# ESP32-S3_Amplifier_and_IMU.net
KiCad netlist of a schematic drawn in Altium Designer
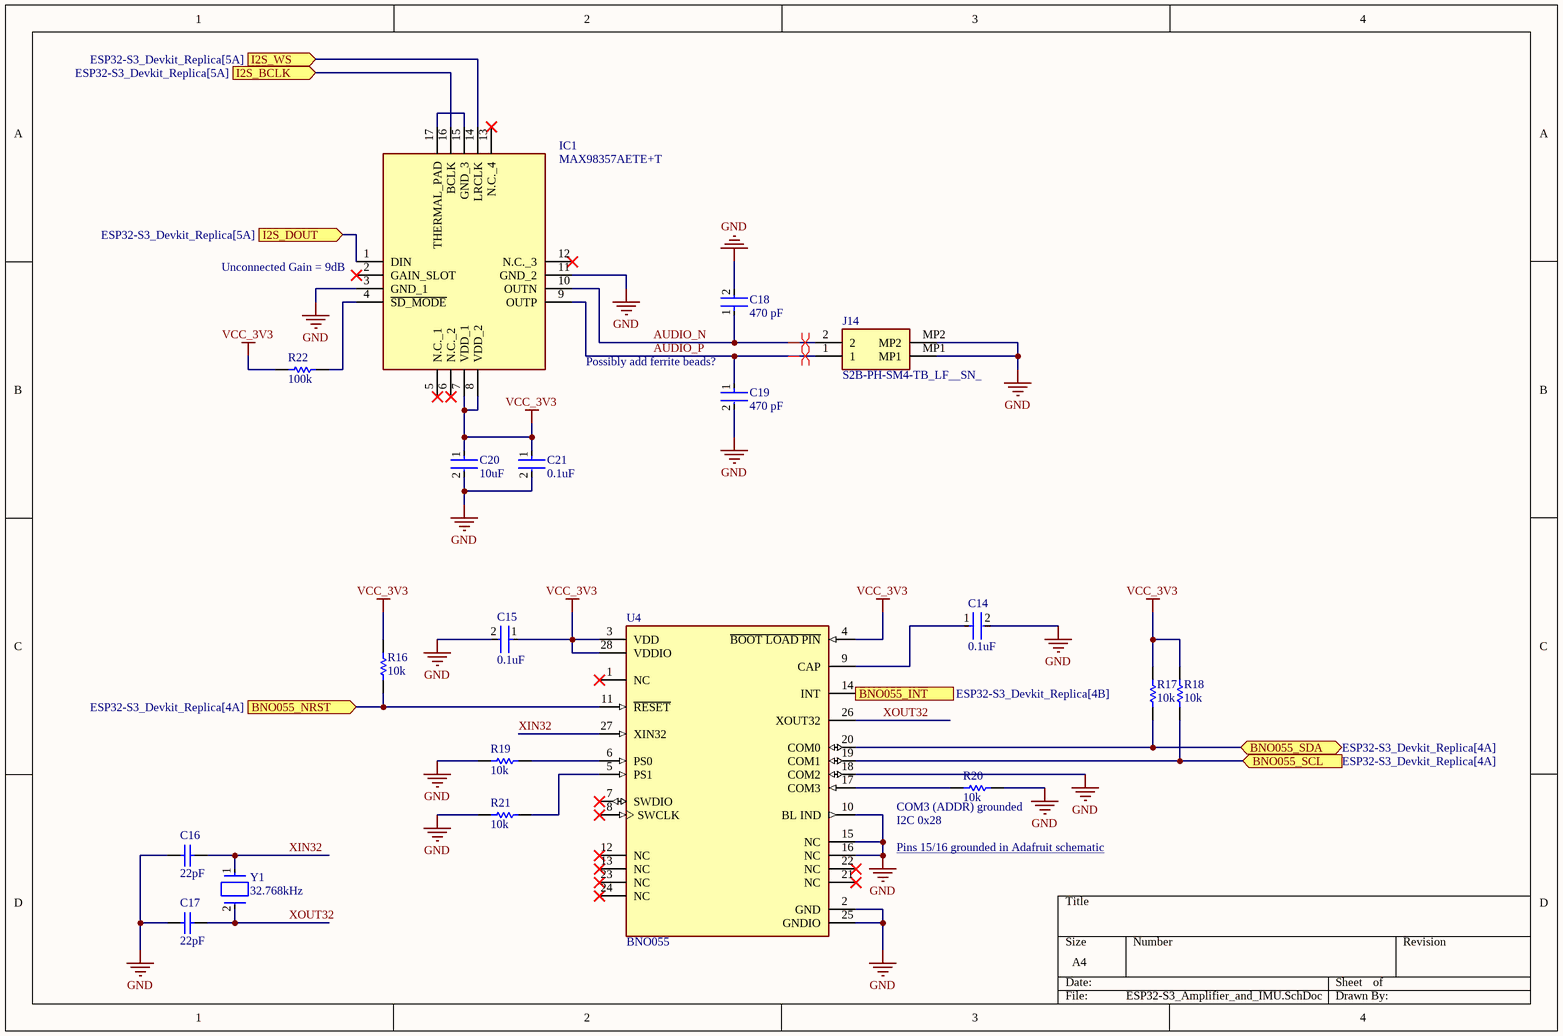
[diagram p0: ESP32-S3_Amplifier_and_IMU.SchDoc]

(export (version "E")
  (design (tool "Eeschema 10.0.6"))
  (components
    (comp (ref "C14")
      (value "C1005X7R1H104K050BB")
      (footprint "FP-C1005-050-0_05-IPC_C")
      (description "Multilayer Ceramic Capacitors 100nF ±10% 50V X7R SMD 0402")
      (fields
        (field (name "VOLTAGE") "50V")
        (field (name "CAPACITANCE") "0.1uF")
        (field (name "TOLERANCE") "10%")
      )
      (libsource (lib "Altium Content Vault") (part "b4654b650e69147ec39a6b967a45e02"))
    )
    (comp (ref "C15")
      (value "C1005X7R1H104K050BB")
      (footprint "FP-C1005-050-0_05-IPC_C")
      (description "Multilayer Ceramic Capacitors 100nF ±10% 50V X7R SMD 0402")
      (fields
        (field (name "VOLTAGE") "50V")
        (field (name "CAPACITANCE") "0.1uF")
        (field (name "TOLERANCE") "10%")
      )
      (libsource (lib "Altium Content Vault") (part "b4654b650e69147ec39a6b967a45e02"))
    )
    (comp (ref "C16")
      (value "CC0402JRNPO9BN220")
      (footprint "CAPC1005X55X25ML05T05")
      (description "Chip Capacitor, 22 pF, +/- 5%, 50 V, -55 to 125 degC, 0402 (1005 Metric), RoHS, Tape and Reel")
      (fields
        (field (name "CAPACITANCE") "22pF")
        (field (name "MANUFACTURER") "Yageo")
        (field (name "TOLERANCE") "5%")
      )
      (libsource (lib "Altium Content Vault") (part "CAP-NP-2"))
    )
    (comp (ref "C17")
      (value "CC0402JRNPO9BN220")
      (footprint "CAPC1005X55X25ML05T05")
      (description "Chip Capacitor, 22 pF, +/- 5%, 50 V, -55 to 125 degC, 0402 (1005 Metric), RoHS, Tape and Reel")
      (fields
        (field (name "CAPACITANCE") "22pF")
        (field (name "MANUFACTURER") "Yageo")
        (field (name "TOLERANCE") "5%")
      )
      (libsource (lib "Altium Content Vault") (part "CAP-NP-2"))
    )
    (comp (ref "C18")
      (value "C0402C471J5GACAUTO")
      (footprint "FP-C0402-BB-MFG")
      (description "CAP CER 470PF 50V C0G/NP0 0402")
      (fields
        (field (name "CAPACITANCE") "470 pF")
        (field (name "TOLERANCE") "0.05")
        (field (name "OCTOPART") "https://octopart.com/c0402c471j5gacauto-kemet-34993933")
      )
      (libsource (lib "Altium Content Vault") (part "b4654b650e69147ec39a6b967a45e02"))
    )
    (comp (ref "C19")
      (value "C0402C471J5GACAUTO")
      (footprint "FP-C0402-BB-MFG")
      (description "CAP CER 470PF 50V C0G/NP0 0402")
      (fields
        (field (name "CAPACITANCE") "470 pF")
        (field (name "TOLERANCE") "0.05")
        (field (name "OCTOPART") "https://octopart.com/c0402c471j5gacauto-kemet-34993933")
      )
      (libsource (lib "Altium Content Vault") (part "b4654b650e69147ec39a6b967a45e02"))
    )
    (comp (ref "C20")
      (value "GRM21BC8YA106KE11L")
      (footprint "FP-GRM21B-0_2-e0_2_0_7-IPC_B")
      (description "Chip Multilayer Ceramic Capacitors for General Purpose, 0805, 10uF, X6S, 22%, 10%, 35V")
      (fields (field (name "CAPACITANCE") "10uF") (field (name "TOLERANCE") "10%"))
      (libsource (lib "Altium Content Vault") (part "b4654b650e69147ec39a6b967a45e02"))
    )
    (comp (ref "C21")
      (value "C1005X7R1H104K050BB")
      (footprint "FP-C1005-050-0_05-IPC_C")
      (description "Multilayer Ceramic Capacitors 100nF ±10% 50V X7R SMD 0402")
      (fields
        (field (name "VOLTAGE") "50V")
        (field (name "CAPACITANCE") "0.1uF")
        (field (name "TOLERANCE") "10%")
      )
      (libsource (lib "Altium Content Vault") (part "b4654b650e69147ec39a6b967a45e02"))
    )
    (comp (ref "IC1")
      (value "MAX98357AETE+T")
      (footprint "GesturaGloveComponents:QFN50P300X300X80-17N")
      (description "Integrated Circuit")
      (fields (field (name "MOUSER PART NUMBER") "700-MAX98357AETE+T"))
      (libsource (lib "GesturaGloveComponents") (part "MAX98357AETE+T"))
    )
    (comp (ref "J14")
      (value "S2B-PH-SM4-TB_LF__SN_")
      (footprint "GesturaGloveComponents:S2BPHSM4TBLFSN")
      (description "Connector")
      (fields (field (name "MANUFACTURER_PART_NUMBER") "S2B-PH-SM4-TB(LF)(SN)"))
      (libsource (lib "GesturaGloveComponents") (part "S2B-PH-SM4-TB_LF__SN_"))
    )
    (comp (ref "R16")
      (value "CRCW040210K0FKEDHP")
      (footprint "RESC1005X40X25ML05T10")
      (description "1")
      (fields (field (name "MANUFACTURER") "Vishay Dale") (field (name "RESISTANCE") "10k"))
      (libsource (lib "Altium Content Vault") (part "RES"))
    )
    (comp (ref "R17")
      (value "CRCW040210K0FKEDHP")
      (footprint "RESC1005X40X25ML05T10")
      (description "1")
      (fields (field (name "MANUFACTURER") "Vishay Dale") (field (name "RESISTANCE") "10k"))
      (libsource (lib "Altium Content Vault") (part "RES"))
    )
    (comp (ref "R18")
      (value "CRCW040210K0FKEDHP")
      (footprint "RESC1005X40X25ML05T10")
      (description "1")
      (fields (field (name "MANUFACTURER") "Vishay Dale") (field (name "RESISTANCE") "10k"))
      (libsource (lib "Altium Content Vault") (part "RES"))
    )
    (comp (ref "R19")
      (value "CRCW040210K0FKEDHP")
      (footprint "RESC1005X40X25ML05T10")
      (description "1")
      (fields (field (name "MANUFACTURER") "Vishay Dale") (field (name "RESISTANCE") "10k"))
      (libsource (lib "Altium Content Vault") (part "RES"))
    )
    (comp (ref "R20")
      (value "CRCW040210K0FKEDHP")
      (footprint "RESC1005X40X25ML05T10")
      (description "1")
      (fields (field (name "MANUFACTURER") "Vishay Dale") (field (name "RESISTANCE") "10k"))
      (libsource (lib "Altium Content Vault") (part "RES"))
    )
    (comp (ref "R21")
      (value "CRCW040210K0FKEDHP")
      (footprint "RESC1005X40X25ML05T10")
      (description "1")
      (fields (field (name "MANUFACTURER") "Vishay Dale") (field (name "RESISTANCE") "10k"))
      (libsource (lib "Altium Content Vault") (part "RES"))
    )
    (comp (ref "R22")
      (value "RC0402FR-07100KL")
      (footprint "RESC1005X40X25NL05T10")
      (fields (field (name "MANUFACTURER") "Yageo / Phycomp") (field (name "RESISTANCE") "100k"))
      (libsource (lib "Altium Content Vault") (part "RES"))
    )
    (comp (ref "U4")
      (value "BNO055")
      (footprint "FP-BNO055-MFG")
      (description "IMU ACCEL/GYRO/MAG I2C 28LGA")
      (libsource (lib "Altium Content Vault") (part "ba837af00a0b6167256f888b31462b1"))
    )
    (comp (ref "Y1")
      (value "ABS07-32.768KHZ-T")
      (footprint "FP-ABS07-MFG")
      (description "Crystal 32.768kHz ±20ppm (Tol) 12.5pF FUND 70kΩ 2-Pin CSMD T/R")
      (fields (field (name "FREQUENCY") "32.768kHz") (field (name "TOLERANCE") "20ppm"))
      (libsource (lib "Altium Content Vault") (part "c23a69dc6c9e2f18f2079038eb95dd1"))
    )
  )
  (nets
    (net (code "1") (name "/AUDIO_N") (class "Default")
      (node (ref "C18") (pin "1") (pinfunction "1_1") (pintype "passive"))
      (node (ref "IC1") (pin "10") (pinfunction "OUTN_10") (pintype "passive"))
      (node (ref "J14") (pin "2") (pinfunction "2_2") (pintype "passive"))
    )
    (net (code "2") (name "/AUDIO_P") (class "Default")
      (node (ref "C19") (pin "1") (pinfunction "1_1") (pintype "passive"))
      (node (ref "IC1") (pin "9") (pinfunction "OUTP_9") (pintype "passive"))
      (node (ref "J14") (pin "1") (pinfunction "1_1") (pintype "passive"))
    )
    (net (code "3") (name "/BNO055_INT") (class "Default")
      (node (ref "U4") (pin "14") (pinfunction "INT_14") (pintype "passive"))
    )
    (net (code "4") (name "/BNO055_NRST") (class "Default")
      (node (ref "R16") (pin "1") (pinfunction "1_1") (pintype "passive"))
      (node (ref "U4") (pin "11") (pinfunction "~{RESET}_11") (pintype "input"))
    )
    (net (code "5") (name "/BNO055_SCL") (class "Default")
      (node (ref "R18") (pin "1") (pinfunction "1_1") (pintype "passive"))
      (node (ref "U4") (pin "19") (pinfunction "COM1_19") (pintype "bidirectional"))
    )
    (net (code "6") (name "/BNO055_SDA") (class "Default")
      (node (ref "R17") (pin "1") (pinfunction "1_1") (pintype "passive"))
      (node (ref "U4") (pin "20") (pinfunction "COM0_20") (pintype "bidirectional"))
    )
    (net (code "7") (name "/I2S_BCLK") (class "Default")
      (node (ref "IC1") (pin "16") (pinfunction "BCLK_16") (pintype "passive"))
    )
    (net (code "8") (name "/I2S_DOUT") (class "Default")
      (node (ref "IC1") (pin "1") (pinfunction "DIN_1") (pintype "passive"))
    )
    (net (code "9") (name "/I2S_WS") (class "Default")
      (node (ref "IC1") (pin "14") (pinfunction "LRCLK_14") (pintype "passive"))
    )
    (net (code "10") (name "/XIN32") (class "Default")
      (node (ref "C16") (pin "1") (pinfunction "1_1") (pintype "passive"))
      (node (ref "U4") (pin "27") (pinfunction "XIN32_27") (pintype "input"))
      (node (ref "Y1") (pin "1") (pinfunction "1_1") (pintype "passive"))
    )
    (net (code "11") (name "/XOUT32") (class "Default")
      (node (ref "C17") (pin "1") (pinfunction "1_1") (pintype "passive"))
      (node (ref "U4") (pin "26") (pinfunction "XOUT32_26") (pintype "passive"))
      (node (ref "Y1") (pin "2") (pinfunction "2_2") (pintype "passive"))
    )
    (net (code "12") (name "GND") (class "Default")
      (node (ref "C14") (pin "2") (pinfunction "2_2") (pintype "passive"))
      (node (ref "C15") (pin "2") (pinfunction "2_2") (pintype "passive"))
      (node (ref "C16") (pin "2") (pinfunction "2_2") (pintype "passive"))
      (node (ref "C17") (pin "2") (pinfunction "2_2") (pintype "passive"))
      (node (ref "C18") (pin "2") (pinfunction "2_2") (pintype "passive"))
      (node (ref "C19") (pin "2") (pinfunction "2_2") (pintype "passive"))
      (node (ref "C20") (pin "2") (pinfunction "2_2") (pintype "passive"))
      (node (ref "C21") (pin "2") (pinfunction "2_2") (pintype "passive"))
      (node (ref "IC1") (pin "11") (pinfunction "GND_2_11") (pintype "passive"))
      (node (ref "IC1") (pin "3") (pinfunction "GND_1_3") (pintype "passive"))
      (node (ref "J14") (pin "MP1") (pinfunction "MP1_MP1") (pintype "passive"))
      (node (ref "J14") (pin "MP2") (pinfunction "MP2_MP2") (pintype "passive"))
      (node (ref "R19") (pin "1") (pinfunction "1_1") (pintype "passive"))
      (node (ref "R20") (pin "2") (pinfunction "2_2") (pintype "passive"))
      (node (ref "R21") (pin "1") (pinfunction "1_1") (pintype "passive"))
      (node (ref "U4") (pin "10") (pinfunction "BL_IND_10") (pintype "output"))
      (node (ref "U4") (pin "15") (pinfunction "NC_15") (pintype "passive"))
      (node (ref "U4") (pin "16") (pinfunction "NC_16") (pintype "passive"))
      (node (ref "U4") (pin "18") (pinfunction "COM2_18") (pintype "bidirectional"))
      (node (ref "U4") (pin "2") (pinfunction "GND_2") (pintype "power_in"))
      (node (ref "U4") (pin "25") (pinfunction "GNDIO_25") (pintype "power_in"))
    )
    (net (code "13") (name "Net-(IC1-GND_3)") (class "Default")
      (node (ref "IC1") (pin "15") (pinfunction "GND_3_15") (pintype "passive"))
      (node (ref "IC1") (pin "17") (pinfunction "THERMAL_PAD_17") (pintype "passive"))
    )
    (net (code "14") (name "Net-(IC1-~{SD_MODE})") (class "Default")
      (node (ref "IC1") (pin "4") (pinfunction "~{SD_MODE}_4") (pintype "passive"))
      (node (ref "R22") (pin "1") (pinfunction "1_1") (pintype "passive"))
    )
    (net (code "15") (name "Net-(U4-CAP)") (class "Default")
      (node (ref "C14") (pin "1") (pinfunction "1_1") (pintype "passive"))
      (node (ref "U4") (pin "9") (pinfunction "CAP_9") (pintype "passive"))
    )
    (net (code "16") (name "Net-(U4-COM3)") (class "Default")
      (node (ref "R20") (pin "1") (pinfunction "1_1") (pintype "passive"))
      (node (ref "U4") (pin "17") (pinfunction "COM3_17") (pintype "input"))
    )
    (net (code "17") (name "Net-(U4-PS0)") (class "Default")
      (node (ref "R19") (pin "2") (pinfunction "2_2") (pintype "passive"))
      (node (ref "U4") (pin "6") (pinfunction "PS0_6") (pintype "input"))
    )
    (net (code "18") (name "Net-(U4-PS1)") (class "Default")
      (node (ref "R21") (pin "2") (pinfunction "2_2") (pintype "passive"))
      (node (ref "U4") (pin "5") (pinfunction "PS1_5") (pintype "input"))
    )
    (net (code "19") (name "VCC_3V3") (class "Default")
      (node (ref "C15") (pin "1") (pinfunction "1_1") (pintype "passive"))
      (node (ref "C20") (pin "1") (pinfunction "1_1") (pintype "passive"))
      (node (ref "C21") (pin "1") (pinfunction "1_1") (pintype "passive"))
      (node (ref "IC1") (pin "7") (pinfunction "VDD_1_7") (pintype "passive"))
      (node (ref "IC1") (pin "8") (pinfunction "VDD_2_8") (pintype "passive"))
      (node (ref "R16") (pin "2") (pinfunction "2_2") (pintype "passive"))
      (node (ref "R17") (pin "2") (pinfunction "2_2") (pintype "passive"))
      (node (ref "R18") (pin "2") (pinfunction "2_2") (pintype "passive"))
      (node (ref "R22") (pin "2") (pinfunction "2_2") (pintype "passive"))
      (node (ref "U4") (pin "28") (pinfunction "VDDIO_28") (pintype "power_in"))
      (node (ref "U4") (pin "3") (pinfunction "VDD_3") (pintype "power_in"))
      (node (ref "U4") (pin "4") (pinfunction "~{BOOT_LOAD_PIN}_4") (pintype "input"))
    )
    (net (code "20") (name "unconnected-(IC1-GAIN_SLOT-Pad2)") (class "Default")
      (node (ref "IC1") (pin "2") (pinfunction "GAIN_SLOT_2") (pintype "passive+no_connect"))
    )
    (net (code "21") (name "unconnected-(IC1-N.C._1-Pad5)") (class "Default")
      (node (ref "IC1") (pin "5") (pinfunction "N.C._1_5") (pintype "passive+no_connect"))
    )
    (net (code "22") (name "unconnected-(IC1-N.C._2-Pad6)") (class "Default")
      (node (ref "IC1") (pin "6") (pinfunction "N.C._2_6") (pintype "passive+no_connect"))
    )
    (net (code "23") (name "unconnected-(IC1-N.C._3-Pad12)") (class "Default")
      (node (ref "IC1") (pin "12") (pinfunction "N.C._3_12") (pintype "passive+no_connect"))
    )
    (net (code "24") (name "unconnected-(IC1-N.C._4-Pad13)") (class "Default")
      (node (ref "IC1") (pin "13") (pinfunction "N.C._4_13") (pintype "passive+no_connect"))
    )
    (net (code "25") (name "unconnected-(U4-NC-Pad1)") (class "Default")
      (node (ref "U4") (pin "1") (pinfunction "NC_1") (pintype "passive+no_connect"))
    )
    (net (code "26") (name "unconnected-(U4-NC-Pad12)") (class "Default")
      (node (ref "U4") (pin "12") (pinfunction "NC_12") (pintype "passive+no_connect"))
    )
    (net (code "27") (name "unconnected-(U4-NC-Pad13)") (class "Default")
      (node (ref "U4") (pin "13") (pinfunction "NC_13") (pintype "passive+no_connect"))
    )
    (net (code "28") (name "unconnected-(U4-NC-Pad21)") (class "Default")
      (node (ref "U4") (pin "21") (pinfunction "NC_21") (pintype "passive+no_connect"))
    )
    (net (code "29") (name "unconnected-(U4-NC-Pad22)") (class "Default")
      (node (ref "U4") (pin "22") (pinfunction "NC_22") (pintype "passive+no_connect"))
    )
    (net (code "30") (name "unconnected-(U4-NC-Pad23)") (class "Default")
      (node (ref "U4") (pin "23") (pinfunction "NC_23") (pintype "passive+no_connect"))
    )
    (net (code "31") (name "unconnected-(U4-NC-Pad24)") (class "Default")
      (node (ref "U4") (pin "24") (pinfunction "NC_24") (pintype "passive+no_connect"))
    )
    (net (code "32") (name "unconnected-(U4-SWCLK-Pad8)") (class "Default")
      (node (ref "U4") (pin "8") (pinfunction "SWCLK_8") (pintype "input+no_connect"))
    )
    (net (code "33") (name "unconnected-(U4-SWDIO-Pad7)") (class "Default")
      (node (ref "U4") (pin "7") (pinfunction "SWDIO_7") (pintype "bidirectional+no_connect"))
    )
  )
)
